# openSipPuff_rev_C.net
KiCad netlist of a schematic drawn in EAGLE
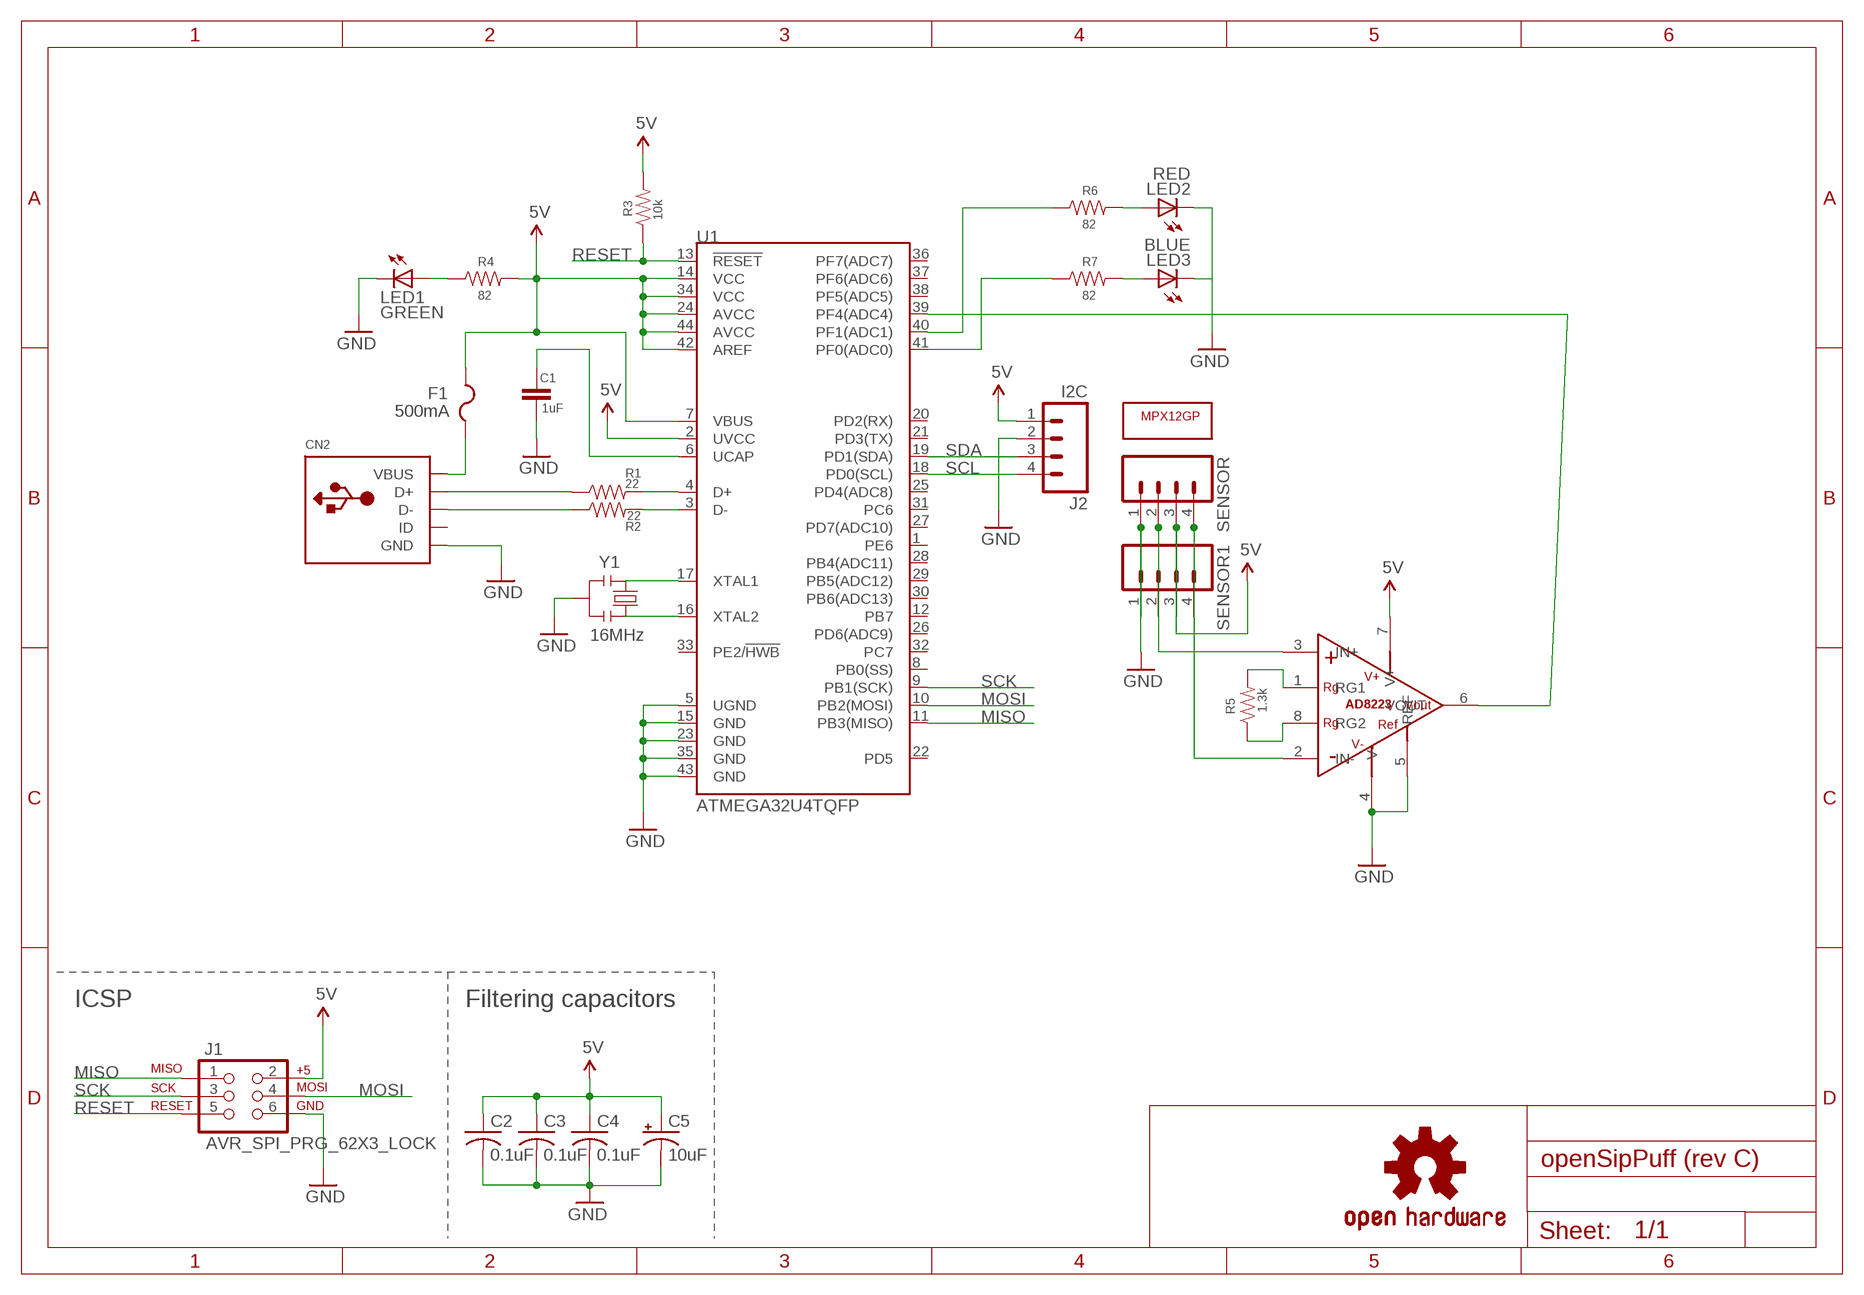
[diagram p0: schematic, sheet 1]

(export (version "E")
  (design (tool "Eeschema 10.0.6"))
  (components
    (comp (ref "C1")
      (value "1uF")
      (footprint "eagle-import:0805")
      (libsource (lib "eagle-import") (part "CAP0805"))
    )
    (comp (ref "C2")
      (value "0.1uF")
      (footprint "eagle-import:C0805K")
      (libsource (lib "eagle-import") (part "C-USC0805K"))
    )
    (comp (ref "C3")
      (value "0.1uF")
      (footprint "eagle-import:C0805K")
      (libsource (lib "eagle-import") (part "C-USC0805K"))
    )
    (comp (ref "C4")
      (value "0.1uF")
      (footprint "eagle-import:C0805K")
      (libsource (lib "eagle-import") (part "C-USC0805K"))
    )
    (comp (ref "C5")
      (value "10uF")
      (footprint "eagle-import:A_3216-18R")
      (libsource (lib "eagle-import") (part "CPOL-USA/3216-18R"))
    )
    (comp (ref "CN2")
      (value "USBMINIB")
      (footprint "eagle-import:USB-MINIB")
      (libsource (lib "eagle-import") (part "USBMINIB"))
    )
    (comp (ref "F1")
      (value "500mA")
      (footprint "eagle-import:R1206")
      (libsource (lib "eagle-import") (part "PTCFUSE-1206"))
    )
    (comp (ref "J1")
      (value "AVR_SPI_PRG_62X3_LOCK")
      (footprint "eagle-import:2X3_LOCK")
      (libsource (lib "eagle-import") (part "AVR_SPI_PRG_62X3_LOCK"))
    )
    (comp (ref "J2")
      (value "I2C")
      (footprint "eagle-import:1X04")
      (libsource (lib "eagle-import") (part "M04PTH"))
    )
    (comp (ref "LED1")
      (value "GREEN")
      (footprint "eagle-import:CHIPLED_0805")
      (libsource (lib "eagle-import") (part "LEDCHIPLED_0805"))
    )
    (comp (ref "LED2")
      (value "RED")
      (footprint "eagle-import:CHIPLED_0805")
      (libsource (lib "eagle-import") (part "LEDCHIPLED_0805"))
    )
    (comp (ref "LED3")
      (value "BLUE")
      (footprint "eagle-import:CHIPLED_0805")
      (libsource (lib "eagle-import") (part "LEDCHIPLED_0805"))
    )
    (comp (ref "LOGO1")
      (value "OSHW-LOGOL")
      (footprint "eagle-import:OSHW-LOGO-L")
      (libsource (lib "eagle-import") (part "OSHW-LOGOL"))
    )
    (comp (ref "R1")
      (value "22")
      (footprint "eagle-import:0805")
      (libsource (lib "eagle-import") (part "RESISTOR0805-RES"))
    )
    (comp (ref "R2")
      (value "22")
      (footprint "eagle-import:0805")
      (libsource (lib "eagle-import") (part "RESISTOR0805-RES"))
    )
    (comp (ref "R3")
      (value "10k")
      (footprint "eagle-import:0805")
      (libsource (lib "eagle-import") (part "RESISTOR0805-RES"))
    )
    (comp (ref "R4")
      (value "82")
      (footprint "eagle-import:0805")
      (libsource (lib "eagle-import") (part "RESISTOR0805-RES"))
    )
    (comp (ref "R5")
      (value "1.3k")
      (footprint "eagle-import:0805")
      (libsource (lib "eagle-import") (part "RESISTOR0805-RES"))
    )
    (comp (ref "R6")
      (value "82")
      (footprint "eagle-import:0805")
      (libsource (lib "eagle-import") (part "RESISTOR0805-RES"))
    )
    (comp (ref "R7")
      (value "82")
      (footprint "eagle-import:0805")
      (libsource (lib "eagle-import") (part "RESISTOR0805-RES"))
    )
    (comp (ref "SENSOR")
      (value "M04PTH")
      (footprint "eagle-import:1X04")
      (libsource (lib "eagle-import") (part "M04PTH"))
    )
    (comp (ref "SENSOR1")
      (value "M04PTH")
      (footprint "eagle-import:1X04")
      (libsource (lib "eagle-import") (part "M04PTH"))
    )
    (comp (ref "U1")
      (value "ATMEGA32U4TQFP")
      (footprint "eagle-import:SPARKFUN-DIGITALIC_TQFP44")
      (libsource (lib "eagle-import") (part "ATMEGA32U4TQFP"))
    )
    (comp (ref "U2")
      (value "AD8223")
      (footprint "eagle-import:MSOP-8")
      (libsource (lib "eagle-import") (part "AD8223"))
    )
    (comp (ref "U3")
      (value "MPX12GP")
      (footprint "eagle-import:MPX12GP")
      (libsource (lib "eagle-import") (part "MPX12GP"))
    )
    (comp (ref "Y1")
      (value "16MHz")
      (footprint "eagle-import:RESONATOR-SMD")
      (libsource (lib "eagle-import") (part "RESONATOR16MHZ"))
    )
  )
  (nets
    (net (code "1") (name "/MISO") (class "Default")
      (node (ref "J1") (pin "1") (pinfunction "1_1") (pintype "passive"))
      (node (ref "U1") (pin "11") (pinfunction "PB3(MISO)_11") (pintype "bidirectional"))
    )
    (net (code "2") (name "/MOSI") (class "Default")
      (node (ref "J1") (pin "4") (pinfunction "4_4") (pintype "passive"))
      (node (ref "U1") (pin "10") (pinfunction "PB2(MOSI)_10") (pintype "bidirectional"))
    )
    (net (code "3") (name "/RESET") (class "Default")
      (node (ref "J1") (pin "5") (pinfunction "5_5") (pintype "passive"))
      (node (ref "R3") (pin "1") (pinfunction "1_1") (pintype "passive"))
      (node (ref "U1") (pin "13") (pinfunction "~{RESET}_13") (pintype "bidirectional"))
    )
    (net (code "4") (name "/SCK") (class "Default")
      (node (ref "J1") (pin "3") (pinfunction "3_3") (pintype "passive"))
      (node (ref "U1") (pin "9") (pinfunction "PB1(SCK)_9") (pintype "bidirectional"))
    )
    (net (code "5") (name "/SCL") (class "Default")
      (node (ref "J2") (pin "4") (pinfunction "4_4") (pintype "passive"))
      (node (ref "U1") (pin "18") (pinfunction "PD0(SCL)_18") (pintype "bidirectional"))
    )
    (net (code "6") (name "/SDA") (class "Default")
      (node (ref "J2") (pin "3") (pinfunction "3_3") (pintype "passive"))
      (node (ref "U1") (pin "19") (pinfunction "PD1(SDA)_19") (pintype "bidirectional"))
    )
    (net (code "7") (name "5V") (class "Default")
      (node (ref "C2") (pin "1") (pinfunction "1_1") (pintype "passive"))
      (node (ref "C3") (pin "1") (pinfunction "1_1") (pintype "passive"))
      (node (ref "C4") (pin "1") (pinfunction "1_1") (pintype "passive"))
      (node (ref "C5") (pin "+") (pinfunction "+_+") (pintype "passive"))
      (node (ref "F1") (pin "2") (pinfunction "2_2") (pintype "passive"))
      (node (ref "J1") (pin "2") (pinfunction "2_2") (pintype "passive"))
      (node (ref "J2") (pin "1") (pinfunction "1_1") (pintype "passive"))
      (node (ref "R3") (pin "2") (pinfunction "2_2") (pintype "passive"))
      (node (ref "R4") (pin "2") (pinfunction "2_2") (pintype "passive"))
      (node (ref "SENSOR") (pin "3") (pinfunction "3_3") (pintype "passive"))
      (node (ref "SENSOR1") (pin "3") (pinfunction "3_3") (pintype "passive"))
      (node (ref "U1") (pin "14") (pinfunction "VCC_14") (pintype "bidirectional"))
      (node (ref "U1") (pin "2") (pinfunction "UVCC_2") (pintype "bidirectional"))
      (node (ref "U1") (pin "24") (pinfunction "AVCC_24") (pintype "bidirectional"))
      (node (ref "U1") (pin "34") (pinfunction "VCC_34") (pintype "bidirectional"))
      (node (ref "U1") (pin "42") (pinfunction "AREF_42") (pintype "bidirectional"))
      (node (ref "U1") (pin "44") (pinfunction "AVCC_44") (pintype "bidirectional"))
      (node (ref "U1") (pin "7") (pinfunction "VBUS_7") (pintype "bidirectional"))
      (node (ref "U2") (pin "7") (pinfunction "V+_7") (pintype "power_in"))
    )
    (net (code "8") (name "GND") (class "Default")
      (node (ref "C1") (pin "2") (pinfunction "2_2") (pintype "passive"))
      (node (ref "C2") (pin "2") (pinfunction "2_2") (pintype "passive"))
      (node (ref "C3") (pin "2") (pinfunction "2_2") (pintype "passive"))
      (node (ref "C4") (pin "2") (pinfunction "2_2") (pintype "passive"))
      (node (ref "C5") (pin "-") (pinfunction "-_-") (pintype "passive"))
      (node (ref "CN2") (pin "GND") (pinfunction "GND_GND") (pintype "power_in"))
      (node (ref "J1") (pin "6") (pinfunction "6_6") (pintype "passive"))
      (node (ref "J2") (pin "2") (pinfunction "2_2") (pintype "passive"))
      (node (ref "LED1") (pin "C") (pinfunction "C_C") (pintype "passive"))
      (node (ref "LED2") (pin "C") (pinfunction "C_C") (pintype "passive"))
      (node (ref "LED3") (pin "C") (pinfunction "C_C") (pintype "passive"))
      (node (ref "SENSOR") (pin "1") (pinfunction "1_1") (pintype "passive"))
      (node (ref "SENSOR1") (pin "1") (pinfunction "1_1") (pintype "passive"))
      (node (ref "U1") (pin "15") (pinfunction "GND_15") (pintype "bidirectional"))
      (node (ref "U1") (pin "23") (pinfunction "GND_23") (pintype "bidirectional"))
      (node (ref "U1") (pin "35") (pinfunction "GND_35") (pintype "bidirectional"))
      (node (ref "U1") (pin "43") (pinfunction "GND_43") (pintype "bidirectional"))
      (node (ref "U1") (pin "5") (pinfunction "UGND_5") (pintype "bidirectional"))
      (node (ref "U2") (pin "4") (pinfunction "V-_4") (pintype "power_in"))
      (node (ref "U2") (pin "5") (pinfunction "REF_5") (pintype "bidirectional"))
      (node (ref "Y1") (pin "2") (pinfunction "2_2") (pintype "passive"))
    )
    (net (code "9") (name "Net-(CN2-PadD+)") (class "Default")
      (node (ref "CN2") (pin "D+") (pinfunction "D+_D+") (pintype "bidirectional"))
      (node (ref "R1") (pin "1") (pinfunction "1_1") (pintype "passive"))
    )
    (net (code "10") (name "Net-(CN2-PadD-)") (class "Default")
      (node (ref "CN2") (pin "D-") (pinfunction "D-_D-") (pintype "bidirectional"))
      (node (ref "R2") (pin "1") (pinfunction "1_1") (pintype "passive"))
    )
    (net (code "11") (name "Net-(CN2-PadVBUS)") (class "Default")
      (node (ref "CN2") (pin "VBUS") (pinfunction "VBUS_VBUS") (pintype "power_in"))
      (node (ref "F1") (pin "1") (pinfunction "1_1") (pintype "passive"))
    )
    (net (code "12") (name "Net-(LED1-PadA)") (class "Default")
      (node (ref "LED1") (pin "A") (pinfunction "A_A") (pintype "passive"))
      (node (ref "R4") (pin "1") (pinfunction "1_1") (pintype "passive"))
    )
    (net (code "13") (name "Net-(LED2-PadA)") (class "Default")
      (node (ref "LED2") (pin "A") (pinfunction "A_A") (pintype "passive"))
      (node (ref "R6") (pin "2") (pinfunction "2_2") (pintype "passive"))
    )
    (net (code "14") (name "Net-(LED3-PadA)") (class "Default")
      (node (ref "LED3") (pin "A") (pinfunction "A_A") (pintype "passive"))
      (node (ref "R7") (pin "2") (pinfunction "2_2") (pintype "passive"))
    )
    (net (code "15") (name "Net-(U1-D+)") (class "Default")
      (node (ref "R1") (pin "2") (pinfunction "2_2") (pintype "passive"))
      (node (ref "U1") (pin "4") (pinfunction "D+_4") (pintype "bidirectional"))
    )
    (net (code "16") (name "Net-(U1-D-)") (class "Default")
      (node (ref "R2") (pin "2") (pinfunction "2_2") (pintype "passive"))
      (node (ref "U1") (pin "3") (pinfunction "D-_3") (pintype "bidirectional"))
    )
    (net (code "17") (name "Net-(U1-PF0(ADC0))") (class "Default")
      (node (ref "R7") (pin "1") (pinfunction "1_1") (pintype "passive"))
      (node (ref "U1") (pin "41") (pinfunction "PF0(ADC0)_41") (pintype "bidirectional"))
    )
    (net (code "18") (name "Net-(U1-PF1(ADC1))") (class "Default")
      (node (ref "R6") (pin "1") (pinfunction "1_1") (pintype "passive"))
      (node (ref "U1") (pin "40") (pinfunction "PF1(ADC1)_40") (pintype "bidirectional"))
    )
    (net (code "19") (name "Net-(U1-PF4(ADC4))") (class "Default")
      (node (ref "U1") (pin "39") (pinfunction "PF4(ADC4)_39") (pintype "bidirectional"))
      (node (ref "U2") (pin "6") (pinfunction "VOUT_6") (pintype "output"))
    )
    (net (code "20") (name "Net-(U1-UCAP)") (class "Default")
      (node (ref "C1") (pin "1") (pinfunction "1_1") (pintype "passive"))
      (node (ref "U1") (pin "6") (pinfunction "UCAP_6") (pintype "bidirectional"))
    )
    (net (code "21") (name "Net-(U1-XTAL1)") (class "Default")
      (node (ref "U1") (pin "17") (pinfunction "XTAL1_17") (pintype "bidirectional"))
      (node (ref "Y1") (pin "1") (pinfunction "1_1") (pintype "passive"))
    )
    (net (code "22") (name "Net-(U1-XTAL2)") (class "Default")
      (node (ref "U1") (pin "16") (pinfunction "XTAL2_16") (pintype "bidirectional"))
      (node (ref "Y1") (pin "3") (pinfunction "3_3") (pintype "passive"))
    )
    (net (code "23") (name "Net-(U2-IN+)") (class "Default")
      (node (ref "SENSOR") (pin "2") (pinfunction "2_2") (pintype "passive"))
      (node (ref "SENSOR1") (pin "2") (pinfunction "2_2") (pintype "passive"))
      (node (ref "U2") (pin "3") (pinfunction "IN+_3") (pintype "input"))
    )
    (net (code "24") (name "Net-(U2-IN-)") (class "Default")
      (node (ref "SENSOR") (pin "4") (pinfunction "4_4") (pintype "passive"))
      (node (ref "SENSOR1") (pin "4") (pinfunction "4_4") (pintype "passive"))
      (node (ref "U2") (pin "2") (pinfunction "IN-_2") (pintype "input"))
    )
    (net (code "25") (name "Net-(U2-RG1)") (class "Default")
      (node (ref "R5") (pin "2") (pinfunction "2_2") (pintype "passive"))
      (node (ref "U2") (pin "1") (pinfunction "RG1_1") (pintype "input"))
    )
    (net (code "26") (name "Net-(U2-RG2)") (class "Default")
      (node (ref "R5") (pin "1") (pinfunction "1_1") (pintype "passive"))
      (node (ref "U2") (pin "8") (pinfunction "RG2_8") (pintype "input"))
    )
    (net (code "27") (name "unconnected-(CN2-PadID)") (class "Default")
      (node (ref "CN2") (pin "ID") (pinfunction "ID_ID") (pintype "bidirectional"))
    )
    (net (code "28") (name "unconnected-(U1-PB0(SS)-Pad8)") (class "Default")
      (node (ref "U1") (pin "8") (pinfunction "PB0(SS)_8") (pintype "bidirectional"))
    )
    (net (code "29") (name "unconnected-(U1-PB4(ADC11)-Pad28)") (class "Default")
      (node (ref "U1") (pin "28") (pinfunction "PB4(ADC11)_28") (pintype "bidirectional"))
    )
    (net (code "30") (name "unconnected-(U1-PB5(ADC12)-Pad29)") (class "Default")
      (node (ref "U1") (pin "29") (pinfunction "PB5(ADC12)_29") (pintype "bidirectional"))
    )
    (net (code "31") (name "unconnected-(U1-PB6(ADC13)-Pad30)") (class "Default")
      (node (ref "U1") (pin "30") (pinfunction "PB6(ADC13)_30") (pintype "bidirectional"))
    )
    (net (code "32") (name "unconnected-(U1-PB7-Pad12)") (class "Default")
      (node (ref "U1") (pin "12") (pinfunction "PB7_12") (pintype "bidirectional"))
    )
    (net (code "33") (name "unconnected-(U1-PC6-Pad31)") (class "Default")
      (node (ref "U1") (pin "31") (pinfunction "PC6_31") (pintype "bidirectional"))
    )
    (net (code "34") (name "unconnected-(U1-PC7-Pad32)") (class "Default")
      (node (ref "U1") (pin "32") (pinfunction "PC7_32") (pintype "bidirectional"))
    )
    (net (code "35") (name "unconnected-(U1-PD2(RX)-Pad20)") (class "Default")
      (node (ref "U1") (pin "20") (pinfunction "PD2(RX)_20") (pintype "bidirectional"))
    )
    (net (code "36") (name "unconnected-(U1-PD3(TX)-Pad21)") (class "Default")
      (node (ref "U1") (pin "21") (pinfunction "PD3(TX)_21") (pintype "bidirectional"))
    )
    (net (code "37") (name "unconnected-(U1-PD4(ADC8)-Pad25)") (class "Default")
      (node (ref "U1") (pin "25") (pinfunction "PD4(ADC8)_25") (pintype "bidirectional"))
    )
    (net (code "38") (name "unconnected-(U1-PD5-Pad22)") (class "Default")
      (node (ref "U1") (pin "22") (pinfunction "PD5_22") (pintype "bidirectional"))
    )
    (net (code "39") (name "unconnected-(U1-PD6(ADC9)-Pad26)") (class "Default")
      (node (ref "U1") (pin "26") (pinfunction "PD6(ADC9)_26") (pintype "bidirectional"))
    )
    (net (code "40") (name "unconnected-(U1-PD7(ADC10)-Pad27)") (class "Default")
      (node (ref "U1") (pin "27") (pinfunction "PD7(ADC10)_27") (pintype "bidirectional"))
    )
    (net (code "41") (name "unconnected-(U1-PE2{slash}~{HWB}-Pad33)") (class "Default")
      (node (ref "U1") (pin "33") (pinfunction "PE2/~{HWB}_33") (pintype "bidirectional"))
    )
    (net (code "42") (name "unconnected-(U1-PE6-Pad1)") (class "Default")
      (node (ref "U1") (pin "1") (pinfunction "PE6_1") (pintype "bidirectional"))
    )
    (net (code "43") (name "unconnected-(U1-PF5(ADC5)-Pad38)") (class "Default")
      (node (ref "U1") (pin "38") (pinfunction "PF5(ADC5)_38") (pintype "bidirectional"))
    )
    (net (code "44") (name "unconnected-(U1-PF6(ADC6)-Pad37)") (class "Default")
      (node (ref "U1") (pin "37") (pinfunction "PF6(ADC6)_37") (pintype "bidirectional"))
    )
    (net (code "45") (name "unconnected-(U1-PF7(ADC7)-Pad36)") (class "Default")
      (node (ref "U1") (pin "36") (pinfunction "PF7(ADC7)_36") (pintype "bidirectional"))
    )
  )
)
